# BEP21_555breakout.net
KiCad netlist of a schematic drawn in EAGLE
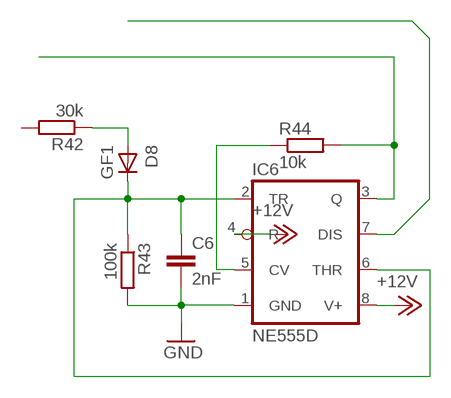
[diagram p0: schematic, sheet 1]

(export (version "E")
  (design (tool "Eeschema 10.0.6"))
  (components
    (comp (ref "C6")
      (value "2nF")
      (footprint "eagle-import:C1206K")
      (libsource (lib "eagle-import") (part "C-EUC1206K"))
    )
    (comp (ref "D8")
      (value "GF1")
      (footprint "eagle-import:SMA-DO214AC")
      (libsource (lib "eagle-import") (part "GF1"))
    )
    (comp (ref "IC6")
      (value "NE555D")
      (footprint "eagle-import:SO08")
      (libsource (lib "eagle-import") (part "555DNE"))
    )
    (comp (ref "R42")
      (value "30k")
      (footprint "eagle-import:R0805")
      (libsource (lib "eagle-import") (part "R-EU_R0805"))
    )
    (comp (ref "R43")
      (value "100k")
      (footprint "eagle-import:R0805")
      (libsource (lib "eagle-import") (part "R-EU_R0805"))
    )
    (comp (ref "R44")
      (value "10k")
      (footprint "eagle-import:R0805")
      (libsource (lib "eagle-import") (part "R-EU_R0805"))
    )
  )
  (nets
    (net (code "1") (name "+12V") (class "Default")
      (node (ref "IC6") (pin "4") (pinfunction "R_4") (pintype "input"))
      (node (ref "IC6") (pin "8") (pinfunction "V+_8") (pintype "power_in"))
    )
    (net (code "2") (name "GND") (class "Default")
      (node (ref "C6") (pin "2") (pinfunction "2_2") (pintype "passive"))
      (node (ref "IC6") (pin "1") (pinfunction "GND_1") (pintype "power_in"))
      (node (ref "R43") (pin "2") (pinfunction "2_2") (pintype "passive"))
    )
    (net (code "3") (name "Net-(D8-C)") (class "Default")
      (node (ref "C6") (pin "1") (pinfunction "1_1") (pintype "passive"))
      (node (ref "D8") (pin "K") (pinfunction "C_K") (pintype "passive"))
      (node (ref "IC6") (pin "2") (pinfunction "TR_2") (pintype "input"))
      (node (ref "IC6") (pin "6") (pinfunction "THR_6") (pintype "input"))
      (node (ref "R43") (pin "1") (pinfunction "1_1") (pintype "passive"))
    )
    (net (code "4") (name "Net-(D8-PadA)") (class "Default")
      (node (ref "D8") (pin "A") (pinfunction "A_A") (pintype "passive"))
      (node (ref "R42") (pin "1") (pinfunction "1_1") (pintype "passive"))
    )
    (net (code "5") (name "Net-(IC6-CV)") (class "Default")
      (node (ref "IC6") (pin "5") (pinfunction "CV_5") (pintype "input"))
      (node (ref "R44") (pin "1") (pinfunction "1_1") (pintype "passive"))
    )
    (net (code "6") (name "Net-(IC6-Q)") (class "Default")
      (node (ref "IC6") (pin "3") (pinfunction "Q_3") (pintype "output"))
      (node (ref "R44") (pin "2") (pinfunction "2_2") (pintype "passive"))
    )
    (net (code "7") (name "unconnected-(IC6-DIS-Pad7)") (class "Default")
      (node (ref "IC6") (pin "7") (pinfunction "DIS_7") (pintype "input"))
    )
    (net (code "8") (name "unconnected-(R42-Pad2)") (class "Default")
      (node (ref "R42") (pin "2") (pinfunction "2_2") (pintype "passive"))
    )
  )
)
